# carteAsserv.net
KiCad netlist of a schematic drawn in Altium Designer
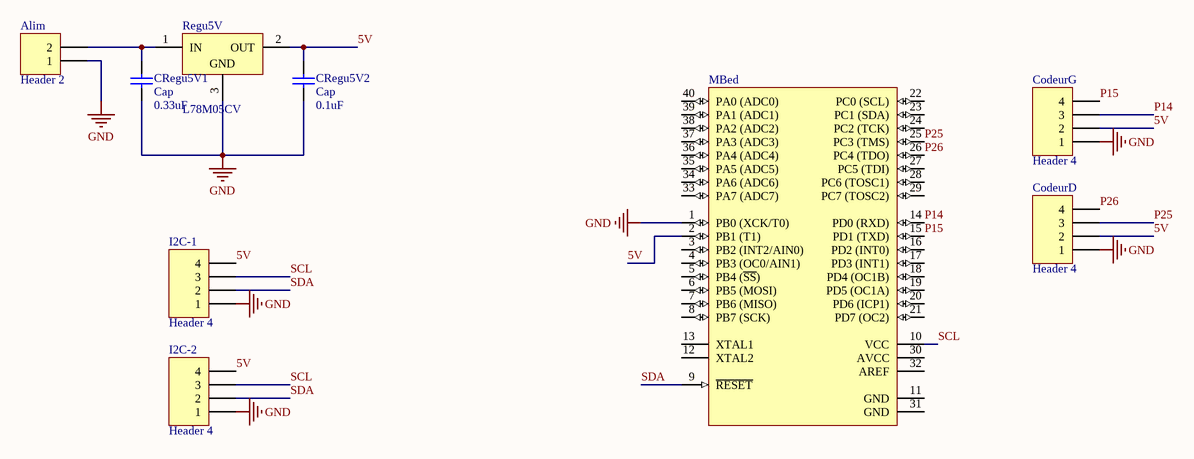
[diagram p0: carteAsserv.SchDoc]

(export (version "E")
  (design (tool "Eeschema 10.0.6"))
  (components
    (comp (ref "Alim")
      (value "Header 2")
      (footprint "HDR1X2")
      (description "Header, 2-Pin")
      (fields (field (name "PUBLISHER") "Altium Limited"))
      (libsource (lib "Miscellaneous Connectors") (part "Header 2"))
    )
    (comp (ref "CodeurD")
      (value "Header 4")
      (footprint "HDR1X4")
      (description "Header, 4-Pin")
      (fields (field (name "PUBLISHER") "Altium Limited"))
      (libsource (lib "Miscellaneous Connectors") (part "Header 4"))
    )
    (comp (ref "CodeurG")
      (value "Header 4")
      (footprint "HDR1X4")
      (description "Header, 4-Pin")
      (fields (field (name "PUBLISHER") "Altium Limited"))
      (libsource (lib "Miscellaneous Connectors") (part "Header 4"))
    )
    (comp (ref "CRegu5V1")
      (value "Cap")
      (footprint "C0805")
      (description "Capacitor")
      (fields (field (name "ALTIUM_VALUE") "0.33uF") (field (name "PUBLISHER") "Altium Limited"))
      (libsource (lib "Miscellaneous Devices") (part "Cap"))
    )
    (comp (ref "CRegu5V2")
      (value "Cap")
      (footprint "C0805")
      (description "Capacitor")
      (fields (field (name "ALTIUM_VALUE") "0.1uF") (field (name "PUBLISHER") "Altium Limited"))
      (libsource (lib "Miscellaneous Devices") (part "Cap"))
    )
    (comp (ref "I2C-1")
      (value "Header 4")
      (footprint "HDR1X4")
      (description "Header, 4-Pin")
      (fields (field (name "PUBLISHER") "Altium Limited"))
      (libsource (lib "Miscellaneous Connectors") (part "Header 4"))
    )
    (comp (ref "I2C-2")
      (value "Header 4")
      (footprint "HDR1X4")
      (description "Header, 4-Pin")
      (fields (field (name "PUBLISHER") "Altium Limited"))
      (libsource (lib "Miscellaneous Connectors") (part "Header 4"))
    )
    (comp (ref "MBed")
      (value "ATmega162V-8PU")
      (footprint "MBed:MBed")
      (fields (field (name "PUBLISHER") "Altium Limited"))
      (libsource (lib "Atmel Microcontroller 8-Bit megaAVR") (part "ATmega162V-8PU"))
    )
    (comp (ref "Regu5V")
      (value "L78M05CV")
      (footprint "TO220V")
      (description "Positive Voltage Regulator")
      (fields (field (name "PUBLISHER") "Altium Limited"))
      (libsource (lib "ST Power Mgt Voltage Regulator") (part "L78M05CV"))
    )
  )
  (nets
    (net (code "1") (name "/5V") (class "Default")
      (node (ref "CRegu5V2") (pin "2") (pinfunction "2_2") (pintype "passive"))
      (node (ref "CodeurD") (pin "2") (pinfunction "2_2") (pintype "passive"))
      (node (ref "CodeurG") (pin "2") (pinfunction "2_2") (pintype "passive"))
      (node (ref "I2C-1") (pin "4") (pinfunction "4_4") (pintype "passive"))
      (node (ref "I2C-2") (pin "4") (pinfunction "4_4") (pintype "passive"))
      (node (ref "MBed") (pin "2") (pinfunction "PB1_(T1)_2") (pintype "bidirectional"))
      (node (ref "Regu5V") (pin "2") (pinfunction "OUT_2") (pintype "power_in"))
    )
    (net (code "2") (name "/P14") (class "Default")
      (node (ref "CodeurG") (pin "3") (pinfunction "3_3") (pintype "passive"))
      (node (ref "MBed") (pin "14") (pinfunction "PD0_(RXD)_14") (pintype "bidirectional"))
    )
    (net (code "3") (name "/P15") (class "Default")
      (node (ref "CodeurG") (pin "4") (pinfunction "4_4") (pintype "passive"))
      (node (ref "MBed") (pin "15") (pinfunction "PD1_(TXD)_15") (pintype "bidirectional"))
    )
    (net (code "4") (name "/P25") (class "Default")
      (node (ref "CodeurD") (pin "3") (pinfunction "3_3") (pintype "passive"))
      (node (ref "MBed") (pin "25") (pinfunction "PC3_(TMS)_25") (pintype "bidirectional"))
    )
    (net (code "5") (name "/P26") (class "Default")
      (node (ref "CodeurD") (pin "4") (pinfunction "4_4") (pintype "passive"))
      (node (ref "MBed") (pin "26") (pinfunction "PC4_(TDO)_26") (pintype "bidirectional"))
    )
    (net (code "6") (name "/SCL") (class "Default")
      (node (ref "I2C-1") (pin "3") (pinfunction "3_3") (pintype "passive"))
      (node (ref "I2C-2") (pin "3") (pinfunction "3_3") (pintype "passive"))
      (node (ref "MBed") (pin "10") (pinfunction "VCC_10") (pintype "power_in"))
    )
    (net (code "7") (name "/SDA") (class "Default")
      (node (ref "I2C-1") (pin "2") (pinfunction "2_2") (pintype "passive"))
      (node (ref "I2C-2") (pin "2") (pinfunction "2_2") (pintype "passive"))
      (node (ref "MBed") (pin "9") (pinfunction "~{RESET}_9") (pintype "input"))
    )
    (net (code "8") (name "GND") (class "Default")
      (node (ref "Alim") (pin "1") (pinfunction "1_1") (pintype "passive"))
      (node (ref "CRegu5V1") (pin "1") (pinfunction "1_1") (pintype "passive"))
      (node (ref "CRegu5V2") (pin "1") (pinfunction "1_1") (pintype "passive"))
      (node (ref "CodeurD") (pin "1") (pinfunction "1_1") (pintype "passive"))
      (node (ref "CodeurG") (pin "1") (pinfunction "1_1") (pintype "passive"))
      (node (ref "I2C-1") (pin "1") (pinfunction "1_1") (pintype "passive"))
      (node (ref "I2C-2") (pin "1") (pinfunction "1_1") (pintype "passive"))
      (node (ref "MBed") (pin "1") (pinfunction "PB0_(XCK/T0)_1") (pintype "bidirectional"))
      (node (ref "Regu5V") (pin "3") (pinfunction "GND_3") (pintype "power_in"))
    )
    (net (code "9") (name "Net-(Regu5V-IN)") (class "Default")
      (node (ref "Alim") (pin "2") (pinfunction "2_2") (pintype "passive"))
      (node (ref "CRegu5V1") (pin "2") (pinfunction "2_2") (pintype "passive"))
      (node (ref "Regu5V") (pin "1") (pinfunction "IN_1") (pintype "power_in"))
    )
    (net (code "10") (name "unconnected-(MBed-AREF-Pad32)") (class "Default")
      (node (ref "MBed") (pin "32") (pinfunction "AREF_32") (pintype "power_in"))
    )
    (net (code "11") (name "unconnected-(MBed-AVCC-Pad30)") (class "Default")
      (node (ref "MBed") (pin "30") (pinfunction "AVCC_30") (pintype "power_in"))
    )
    (net (code "12") (name "unconnected-(MBed-GND-Pad11)") (class "Default")
      (node (ref "MBed") (pin "11") (pinfunction "GND_11") (pintype "power_in"))
    )
    (net (code "13") (name "unconnected-(MBed-GND-Pad31)") (class "Default")
      (node (ref "MBed") (pin "31") (pinfunction "GND_31") (pintype "power_in"))
    )
    (net (code "14") (name "unconnected-(MBed-PA0_(ADC0)-Pad40)") (class "Default")
      (node (ref "MBed") (pin "40") (pinfunction "PA0_(ADC0)_40") (pintype "bidirectional"))
    )
    (net (code "15") (name "unconnected-(MBed-PA1_(ADC1)-Pad39)") (class "Default")
      (node (ref "MBed") (pin "39") (pinfunction "PA1_(ADC1)_39") (pintype "bidirectional"))
    )
    (net (code "16") (name "unconnected-(MBed-PA2_(ADC2)-Pad38)") (class "Default")
      (node (ref "MBed") (pin "38") (pinfunction "PA2_(ADC2)_38") (pintype "bidirectional"))
    )
    (net (code "17") (name "unconnected-(MBed-PA3_(ADC3)-Pad37)") (class "Default")
      (node (ref "MBed") (pin "37") (pinfunction "PA3_(ADC3)_37") (pintype "bidirectional"))
    )
    (net (code "18") (name "unconnected-(MBed-PA4_(ADC4)-Pad36)") (class "Default")
      (node (ref "MBed") (pin "36") (pinfunction "PA4_(ADC4)_36") (pintype "bidirectional"))
    )
    (net (code "19") (name "unconnected-(MBed-PA5_(ADC5)-Pad35)") (class "Default")
      (node (ref "MBed") (pin "35") (pinfunction "PA5_(ADC5)_35") (pintype "bidirectional"))
    )
    (net (code "20") (name "unconnected-(MBed-PA6_(ADC6)-Pad34)") (class "Default")
      (node (ref "MBed") (pin "34") (pinfunction "PA6_(ADC6)_34") (pintype "bidirectional"))
    )
    (net (code "21") (name "unconnected-(MBed-PA7_(ADC7)-Pad33)") (class "Default")
      (node (ref "MBed") (pin "33") (pinfunction "PA7_(ADC7)_33") (pintype "bidirectional"))
    )
    (net (code "22") (name "unconnected-(MBed-PB2_(INT2{slash}AIN0)-Pad3)") (class "Default")
      (node (ref "MBed") (pin "3") (pinfunction "PB2_(INT2/AIN0)_3") (pintype "bidirectional"))
    )
    (net (code "23") (name "unconnected-(MBed-PB3_(OC0{slash}AIN1)-Pad4)") (class "Default")
      (node (ref "MBed") (pin "4") (pinfunction "PB3_(OC0/AIN1)_4") (pintype "bidirectional"))
    )
    (net (code "24") (name "unconnected-(MBed-PB4_(~{SS})-Pad5)") (class "Default")
      (node (ref "MBed") (pin "5") (pinfunction "PB4_(~{SS})_5") (pintype "bidirectional"))
    )
    (net (code "25") (name "unconnected-(MBed-PB5_(MOSI)-Pad6)") (class "Default")
      (node (ref "MBed") (pin "6") (pinfunction "PB5_(MOSI)_6") (pintype "bidirectional"))
    )
    (net (code "26") (name "unconnected-(MBed-PB6_(MISO)-Pad7)") (class "Default")
      (node (ref "MBed") (pin "7") (pinfunction "PB6_(MISO)_7") (pintype "bidirectional"))
    )
    (net (code "27") (name "unconnected-(MBed-PB7_(SCK)-Pad8)") (class "Default")
      (node (ref "MBed") (pin "8") (pinfunction "PB7_(SCK)_8") (pintype "bidirectional"))
    )
    (net (code "28") (name "unconnected-(MBed-PC0_(SCL)-Pad22)") (class "Default")
      (node (ref "MBed") (pin "22") (pinfunction "PC0_(SCL)_22") (pintype "bidirectional"))
    )
    (net (code "29") (name "unconnected-(MBed-PC1_(SDA)-Pad23)") (class "Default")
      (node (ref "MBed") (pin "23") (pinfunction "PC1_(SDA)_23") (pintype "bidirectional"))
    )
    (net (code "30") (name "unconnected-(MBed-PC2_(TCK)-Pad24)") (class "Default")
      (node (ref "MBed") (pin "24") (pinfunction "PC2_(TCK)_24") (pintype "bidirectional"))
    )
    (net (code "31") (name "unconnected-(MBed-PC5_(TDI)-Pad27)") (class "Default")
      (node (ref "MBed") (pin "27") (pinfunction "PC5_(TDI)_27") (pintype "bidirectional"))
    )
    (net (code "32") (name "unconnected-(MBed-PC6_(TOSC1)-Pad28)") (class "Default")
      (node (ref "MBed") (pin "28") (pinfunction "PC6_(TOSC1)_28") (pintype "bidirectional"))
    )
    (net (code "33") (name "unconnected-(MBed-PC7_(TOSC2)-Pad29)") (class "Default")
      (node (ref "MBed") (pin "29") (pinfunction "PC7_(TOSC2)_29") (pintype "bidirectional"))
    )
    (net (code "34") (name "unconnected-(MBed-PD2_(INT0)-Pad16)") (class "Default")
      (node (ref "MBed") (pin "16") (pinfunction "PD2_(INT0)_16") (pintype "bidirectional"))
    )
    (net (code "35") (name "unconnected-(MBed-PD3_(INT1)-Pad17)") (class "Default")
      (node (ref "MBed") (pin "17") (pinfunction "PD3_(INT1)_17") (pintype "bidirectional"))
    )
    (net (code "36") (name "unconnected-(MBed-PD4_(OC1B)-Pad18)") (class "Default")
      (node (ref "MBed") (pin "18") (pinfunction "PD4_(OC1B)_18") (pintype "bidirectional"))
    )
    (net (code "37") (name "unconnected-(MBed-PD5_(OC1A)-Pad19)") (class "Default")
      (node (ref "MBed") (pin "19") (pinfunction "PD5_(OC1A)_19") (pintype "bidirectional"))
    )
    (net (code "38") (name "unconnected-(MBed-PD6_(ICP1)-Pad20)") (class "Default")
      (node (ref "MBed") (pin "20") (pinfunction "PD6_(ICP1)_20") (pintype "bidirectional"))
    )
    (net (code "39") (name "unconnected-(MBed-PD7_(OC2)-Pad21)") (class "Default")
      (node (ref "MBed") (pin "21") (pinfunction "PD7_(OC2)_21") (pintype "bidirectional"))
    )
    (net (code "40") (name "unconnected-(MBed-XTAL1-Pad13)") (class "Default")
      (node (ref "MBed") (pin "13") (pinfunction "XTAL1_13") (pintype "passive"))
    )
    (net (code "41") (name "unconnected-(MBed-XTAL2-Pad12)") (class "Default")
      (node (ref "MBed") (pin "12") (pinfunction "XTAL2_12") (pintype "passive"))
    )
  )
)
